# Printhead_board.net
KiCad netlist of a schematic drawn in EAGLE
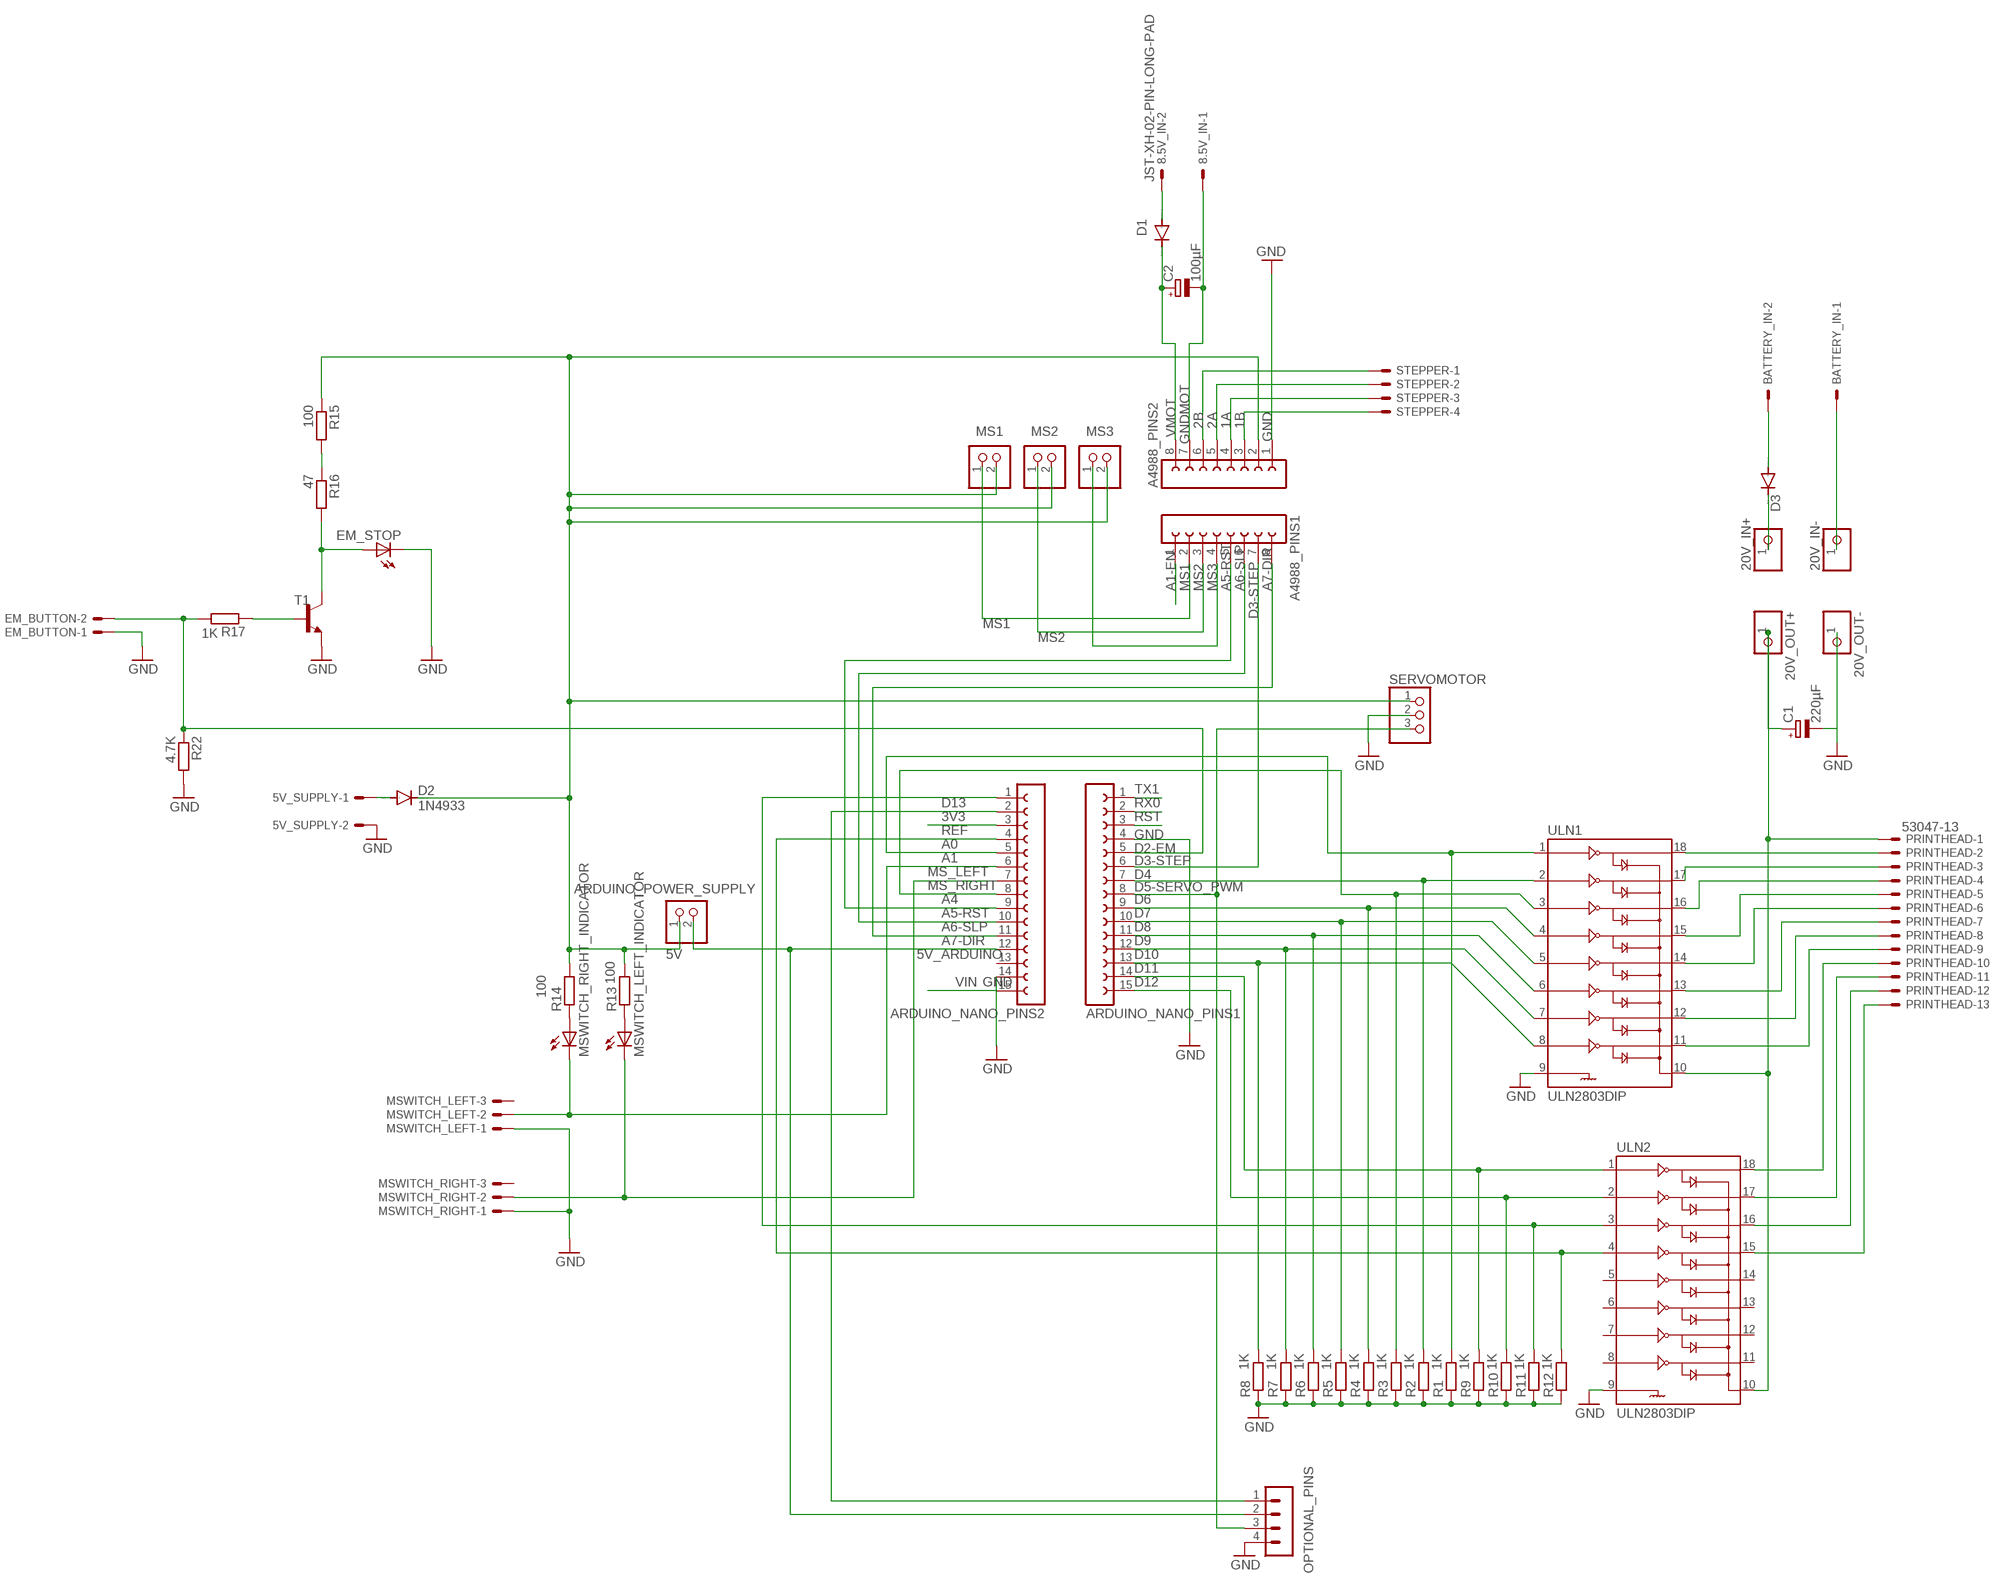
[diagram p0: schematic, sheet 1]

(export (version "E")
  (design (tool "Eeschema 10.0.6"))
  (components
    (comp (ref "5V_SUPPLY")
      (value "JST-XH-02-PIN-LONG-PAD")
      (footprint "eagle-import:JST-XH-02-PACKAGE-LONG-PAD")
      (libsource (lib "eagle-import") (part "JST-XH-02-PIN-LONG-PAD"))
    )
    (comp (ref "8.5V_IN")
      (value "JST-XH-02-PIN-LONG-PAD")
      (footprint "eagle-import:JST-XH-02-PACKAGE-LONG-PAD")
      (libsource (lib "eagle-import") (part "JST-XH-02-PIN-LONG-PAD"))
    )
    (comp (ref "20V_IN+")
      (value "PINHD-1X1")
      (footprint "eagle-import:1X01")
      (libsource (lib "eagle-import") (part "PINHD-1X1"))
    )
    (comp (ref "20V_IN-")
      (value "PINHD-1X1")
      (footprint "eagle-import:1X01")
      (libsource (lib "eagle-import") (part "PINHD-1X1"))
    )
    (comp (ref "20V_OUT+")
      (value "PINHD-1X1")
      (footprint "eagle-import:1X01")
      (libsource (lib "eagle-import") (part "PINHD-1X1"))
    )
    (comp (ref "20V_OUT-")
      (value "PINHD-1X1")
      (footprint "eagle-import:1X01")
      (libsource (lib "eagle-import") (part "PINHD-1X1"))
    )
    (comp (ref "A4988_PINS1")
      (value "FE08-1")
      (footprint "eagle-import:FE08")
      (libsource (lib "eagle-import") (part "FE08-1"))
    )
    (comp (ref "A4988_PINS2")
      (value "FE08-1")
      (footprint "eagle-import:FE08")
      (libsource (lib "eagle-import") (part "FE08-1"))
    )
    (comp (ref "ARDUINO_NANO_PINS1")
      (value "FE15-1")
      (footprint "eagle-import:FE15")
      (libsource (lib "eagle-import") (part "FE15-1"))
    )
    (comp (ref "ARDUINO_NANO_PINS2")
      (value "FE15-1")
      (footprint "eagle-import:FE15")
      (libsource (lib "eagle-import") (part "FE15-1"))
    )
    (comp (ref "ARDUINO_POWER_SUPPLY")
      (value "PINHD-1X2")
      (footprint "eagle-import:1X02")
      (libsource (lib "eagle-import") (part "PINHD-1X2"))
    )
    (comp (ref "BATTERY_IN")
      (value "JST-XH-02-PIN-ROUND-PAD")
      (footprint "eagle-import:JST-XH-02-PACKAGE-ROUND-PAD")
      (libsource (lib "eagle-import") (part "JST-XH-02-PIN-ROUND-PAD"))
    )
    (comp (ref "C1")
      (value "220µF")
      (footprint "eagle-import:E5-10,5")
      (libsource (lib "eagle-import") (part "CPOL-EUE5-10.5"))
    )
    (comp (ref "C2")
      (value "100µF")
      (footprint "eagle-import:SANYO-OSCON_E")
      (libsource (lib "eagle-import") (part "CPOL-EUSANYO_E"))
    )
    (comp (ref "D1")
      (value "DIODE-DO15-12")
      (footprint "eagle-import:DO15-12")
      (libsource (lib "eagle-import") (part "DIODE-DO15-12"))
    )
    (comp (ref "D2")
      (value "1N4933")
      (footprint "eagle-import:DO41-10")
      (libsource (lib "eagle-import") (part "1N4933"))
    )
    (comp (ref "D3")
      (value "DIODE-DO201-15")
      (footprint "eagle-import:DO201-15")
      (libsource (lib "eagle-import") (part "DIODE-DO201-15"))
    )
    (comp (ref "EM_BUTTON")
      (value "JST-XH-02-PIN-LONG-PAD")
      (footprint "eagle-import:JST-XH-02-PACKAGE-LONG-PAD")
      (libsource (lib "eagle-import") (part "JST-XH-02-PIN-LONG-PAD"))
    )
    (comp (ref "EM_STOP")
      (value "LED5MM")
      (footprint "eagle-import:LED5MM")
      (libsource (lib "eagle-import") (part "LED5MM"))
    )
    (comp (ref "MS1")
      (value "PINHD-1X2")
      (footprint "eagle-import:1X02")
      (libsource (lib "eagle-import") (part "PINHD-1X2"))
    )
    (comp (ref "MS2")
      (value "PINHD-1X2")
      (footprint "eagle-import:1X02")
      (libsource (lib "eagle-import") (part "PINHD-1X2"))
    )
    (comp (ref "MS3")
      (value "PINHD-1X2")
      (footprint "eagle-import:1X02")
      (libsource (lib "eagle-import") (part "PINHD-1X2"))
    )
    (comp (ref "MSWITCH_LEFT")
      (value "JST-XH-03-PIN-LONG-PAD")
      (footprint "eagle-import:JST-XH-03-PACKAGE-LONG-PAD")
      (libsource (lib "eagle-import") (part "JST-XH-03-PIN-LONG-PAD"))
    )
    (comp (ref "MSWITCH_LEFT_INDICATOR")
      (value "LED5MM")
      (footprint "eagle-import:LED5MM")
      (libsource (lib "eagle-import") (part "LED5MM"))
    )
    (comp (ref "MSWITCH_RIGHT")
      (value "JST-XH-03-PIN-LONG-PAD")
      (footprint "eagle-import:JST-XH-03-PACKAGE-LONG-PAD")
      (libsource (lib "eagle-import") (part "JST-XH-03-PIN-LONG-PAD"))
    )
    (comp (ref "MSWITCH_RIGHT_INDICATOR")
      (value "LED5MM")
      (footprint "eagle-import:LED5MM")
      (libsource (lib "eagle-import") (part "LED5MM"))
    )
    (comp (ref "OPTIONAL_PINS")
      (value "MA04-1")
      (footprint "eagle-import:MA04-1")
      (libsource (lib "eagle-import") (part "MA04-1"))
    )
    (comp (ref "PRINTHEAD")
      (value "53047-13")
      (footprint "eagle-import:53047-13")
      (fields (field (name "MF") "MOLEX") (field (name "MPN") "53047-1310-C"))
      (libsource (lib "eagle-import") (part "53?-13047"))
    )
    (comp (ref "R1")
      (value "1K")
      (footprint "eagle-import:0207_7")
      (libsource (lib "eagle-import") (part "R-EU_0207/7"))
    )
    (comp (ref "R2")
      (value "1K")
      (footprint "eagle-import:0207_7")
      (libsource (lib "eagle-import") (part "R-EU_0207/7"))
    )
    (comp (ref "R3")
      (value "1K")
      (footprint "eagle-import:0207_7")
      (libsource (lib "eagle-import") (part "R-EU_0207/7"))
    )
    (comp (ref "R4")
      (value "1K")
      (footprint "eagle-import:0207_7")
      (libsource (lib "eagle-import") (part "R-EU_0207/7"))
    )
    (comp (ref "R5")
      (value "1K")
      (footprint "eagle-import:0207_7")
      (libsource (lib "eagle-import") (part "R-EU_0207/7"))
    )
    (comp (ref "R6")
      (value "1K")
      (footprint "eagle-import:0207_7")
      (libsource (lib "eagle-import") (part "R-EU_0207/7"))
    )
    (comp (ref "R7")
      (value "1K")
      (footprint "eagle-import:0207_7")
      (libsource (lib "eagle-import") (part "R-EU_0207/7"))
    )
    (comp (ref "R8")
      (value "1K")
      (footprint "eagle-import:0207_7")
      (libsource (lib "eagle-import") (part "R-EU_0207/7"))
    )
    (comp (ref "R9")
      (value "1K")
      (footprint "eagle-import:0207_7")
      (libsource (lib "eagle-import") (part "R-EU_0207/7"))
    )
    (comp (ref "R10")
      (value "1K")
      (footprint "eagle-import:0207_7")
      (libsource (lib "eagle-import") (part "R-EU_0207/7"))
    )
    (comp (ref "R11")
      (value "1K")
      (footprint "eagle-import:0207_7")
      (libsource (lib "eagle-import") (part "R-EU_0207/7"))
    )
    (comp (ref "R12")
      (value "1K")
      (footprint "eagle-import:0207_7")
      (libsource (lib "eagle-import") (part "R-EU_0207/7"))
    )
    (comp (ref "R13")
      (value "100")
      (footprint "eagle-import:0207_7")
      (libsource (lib "eagle-import") (part "R-EU_0207/7"))
    )
    (comp (ref "R14")
      (value "100")
      (footprint "eagle-import:0207_7")
      (libsource (lib "eagle-import") (part "R-EU_0207/7"))
    )
    (comp (ref "R15")
      (value "100")
      (footprint "eagle-import:0207_7")
      (libsource (lib "eagle-import") (part "R-EU_0207/7"))
    )
    (comp (ref "R16")
      (value "47")
      (footprint "eagle-import:0207_7")
      (libsource (lib "eagle-import") (part "R-EU_0207/7"))
    )
    (comp (ref "R17")
      (value "1K")
      (footprint "eagle-import:0207_7")
      (libsource (lib "eagle-import") (part "R-EU_0207/7"))
    )
    (comp (ref "R22")
      (value "4.7K")
      (footprint "eagle-import:0207_7")
      (libsource (lib "eagle-import") (part "R-EU_0207/7"))
    )
    (comp (ref "SERVOMOTOR")
      (value "PINHD-1X3")
      (footprint "eagle-import:1X03")
      (libsource (lib "eagle-import") (part "PINHD-1X3"))
    )
    (comp (ref "STEPPER")
      (value "JST-XH-04-PIN-LONG-PAD")
      (footprint "eagle-import:JST-XH-04-PACKAGE-LONG-PAD")
      (libsource (lib "eagle-import") (part "JST-XH-04-PIN-LONG-PAD"))
    )
    (comp (ref "T1")
      (value "2N2222")
      (footprint "eagle-import:TO92-EBC-OVAL")
      (libsource (lib "eagle-import") (part "2N2222"))
    )
    (comp (ref "ULN1")
      (value "ULN2803DIP")
      (footprint "eagle-import:DIL18")
      (fields (field (name "MF") "STMicroelectronics") (field (name "MP") "ULN2803"))
      (libsource (lib "eagle-import") (part "ULN2803DIP"))
    )
    (comp (ref "ULN2")
      (value "ULN2803DIP")
      (footprint "eagle-import:DIL18")
      (fields (field (name "MF") "STMicroelectronics") (field (name "MP") "ULN2803"))
      (libsource (lib "eagle-import") (part "ULN2803DIP"))
    )
  )
  (nets
    (net (code "1") (name "/1A") (class "Default")
      (node (ref "A4988_PINS2") (pin "4") (pinfunction "4_4") (pintype "passive"))
      (node (ref "STEPPER") (pin "3") (pinfunction "S_3") (pintype "passive"))
    )
    (net (code "2") (name "/1B") (class "Default")
      (node (ref "A4988_PINS2") (pin "3") (pinfunction "3_3") (pintype "passive"))
      (node (ref "STEPPER") (pin "4") (pinfunction "S_4") (pintype "passive"))
    )
    (net (code "3") (name "/2A") (class "Default")
      (node (ref "A4988_PINS2") (pin "5") (pinfunction "5_5") (pintype "passive"))
      (node (ref "STEPPER") (pin "2") (pinfunction "S_2") (pintype "passive"))
    )
    (net (code "4") (name "/2B") (class "Default")
      (node (ref "A4988_PINS2") (pin "6") (pinfunction "6_6") (pintype "passive"))
      (node (ref "STEPPER") (pin "1") (pinfunction "S_1") (pintype "passive"))
    )
    (net (code "5") (name "/3V3") (class "Default")
      (node (ref "ARDUINO_NANO_PINS2") (pin "2") (pinfunction "2_2") (pintype "passive"))
      (node (ref "OPTIONAL_PINS") (pin "1") (pinfunction "1_1") (pintype "passive"))
    )
    (net (code "6") (name "/5V") (class "Default")
      (node (ref "A4988_PINS2") (pin "2") (pinfunction "2_2") (pintype "passive"))
      (node (ref "ARDUINO_POWER_SUPPLY") (pin "1") (pinfunction "1_1") (pintype "passive"))
      (node (ref "D2") (pin "C") (pinfunction "C_C") (pintype "passive"))
      (node (ref "MS1") (pin "2") (pinfunction "2_2") (pintype "passive"))
      (node (ref "MS2") (pin "2") (pinfunction "2_2") (pintype "passive"))
      (node (ref "MS3") (pin "2") (pinfunction "2_2") (pintype "passive"))
      (node (ref "R13") (pin "2") (pinfunction "2_2") (pintype "passive"))
      (node (ref "R14") (pin "2") (pinfunction "2_2") (pintype "passive"))
      (node (ref "R15") (pin "1") (pinfunction "1_1") (pintype "passive"))
      (node (ref "SERVOMOTOR") (pin "1") (pinfunction "1_1") (pintype "passive"))
    )
    (net (code "7") (name "/5V_ARDUINO") (class "Default")
      (node (ref "ARDUINO_NANO_PINS2") (pin "12") (pinfunction "12_12") (pintype "passive"))
      (node (ref "ARDUINO_POWER_SUPPLY") (pin "2") (pinfunction "2_2") (pintype "passive"))
      (node (ref "OPTIONAL_PINS") (pin "2") (pinfunction "2_2") (pintype "passive"))
    )
    (net (code "8") (name "/A0") (class "Default")
      (node (ref "ARDUINO_NANO_PINS2") (pin "4") (pinfunction "4_4") (pintype "passive"))
      (node (ref "R12") (pin "2") (pinfunction "2_2") (pintype "passive"))
      (node (ref "ULN2") (pin "4") (pinfunction "4_4") (pintype "bidirectional"))
    )
    (net (code "9") (name "/A1") (class "Default")
      (node (ref "ARDUINO_NANO_PINS2") (pin "5") (pinfunction "5_5") (pintype "passive"))
      (node (ref "R1") (pin "2") (pinfunction "2_2") (pintype "passive"))
      (node (ref "ULN1") (pin "1") (pinfunction "1_1") (pintype "bidirectional"))
    )
    (net (code "10") (name "/A1-EN") (class "Default")
      (node (ref "A4988_PINS1") (pin "1") (pinfunction "1_1") (pintype "passive"))
    )
    (net (code "11") (name "/A4") (class "Default")
      (node (ref "ARDUINO_NANO_PINS2") (pin "8") (pinfunction "8_8") (pintype "passive"))
      (node (ref "R3") (pin "2") (pinfunction "2_2") (pintype "passive"))
      (node (ref "ULN1") (pin "3") (pinfunction "3_3") (pintype "bidirectional"))
    )
    (net (code "12") (name "/A5-RST") (class "Default")
      (node (ref "A4988_PINS1") (pin "5") (pinfunction "5_5") (pintype "passive"))
      (node (ref "ARDUINO_NANO_PINS2") (pin "9") (pinfunction "9_9") (pintype "passive"))
    )
    (net (code "13") (name "/A6-SLP") (class "Default")
      (node (ref "A4988_PINS1") (pin "6") (pinfunction "6_6") (pintype "passive"))
      (node (ref "ARDUINO_NANO_PINS2") (pin "10") (pinfunction "10_10") (pintype "passive"))
    )
    (net (code "14") (name "/A7-DIR") (class "Default")
      (node (ref "A4988_PINS1") (pin "8") (pinfunction "8_8") (pintype "passive"))
      (node (ref "ARDUINO_NANO_PINS2") (pin "11") (pinfunction "11_11") (pintype "passive"))
    )
    (net (code "15") (name "/D2-EM") (class "Default")
      (node (ref "ARDUINO_NANO_PINS1") (pin "5") (pinfunction "5_5") (pintype "passive"))
      (node (ref "EM_BUTTON") (pin "2") (pinfunction "S_2") (pintype "passive"))
      (node (ref "R17") (pin "2") (pinfunction "2_2") (pintype "passive"))
      (node (ref "R22") (pin "1") (pinfunction "1_1") (pintype "passive"))
    )
    (net (code "16") (name "/D3-STEP") (class "Default")
      (node (ref "A4988_PINS1") (pin "7") (pinfunction "7_7") (pintype "passive"))
      (node (ref "ARDUINO_NANO_PINS1") (pin "6") (pinfunction "6_6") (pintype "passive"))
    )
    (net (code "17") (name "/D4") (class "Default")
      (node (ref "ARDUINO_NANO_PINS1") (pin "7") (pinfunction "7_7") (pintype "passive"))
      (node (ref "R2") (pin "2") (pinfunction "2_2") (pintype "passive"))
      (node (ref "ULN1") (pin "2") (pinfunction "2_2") (pintype "bidirectional"))
    )
    (net (code "18") (name "/D5-SERVO_PWM") (class "Default")
      (node (ref "ARDUINO_NANO_PINS1") (pin "8") (pinfunction "8_8") (pintype "passive"))
      (node (ref "OPTIONAL_PINS") (pin "3") (pinfunction "3_3") (pintype "passive"))
      (node (ref "SERVOMOTOR") (pin "3") (pinfunction "3_3") (pintype "passive"))
    )
    (net (code "19") (name "/D6") (class "Default")
      (node (ref "ARDUINO_NANO_PINS1") (pin "9") (pinfunction "9_9") (pintype "passive"))
      (node (ref "R4") (pin "2") (pinfunction "2_2") (pintype "passive"))
      (node (ref "ULN1") (pin "4") (pinfunction "4_4") (pintype "bidirectional"))
    )
    (net (code "20") (name "/D7") (class "Default")
      (node (ref "ARDUINO_NANO_PINS1") (pin "10") (pinfunction "10_10") (pintype "passive"))
      (node (ref "R5") (pin "2") (pinfunction "2_2") (pintype "passive"))
      (node (ref "ULN1") (pin "5") (pinfunction "5_5") (pintype "bidirectional"))
    )
    (net (code "21") (name "/D8") (class "Default")
      (node (ref "ARDUINO_NANO_PINS1") (pin "11") (pinfunction "11_11") (pintype "passive"))
      (node (ref "R6") (pin "2") (pinfunction "2_2") (pintype "passive"))
      (node (ref "ULN1") (pin "6") (pinfunction "6_6") (pintype "bidirectional"))
    )
    (net (code "22") (name "/D9") (class "Default")
      (node (ref "ARDUINO_NANO_PINS1") (pin "12") (pinfunction "12_12") (pintype "passive"))
      (node (ref "R7") (pin "2") (pinfunction "2_2") (pintype "passive"))
      (node (ref "ULN1") (pin "7") (pinfunction "7_7") (pintype "bidirectional"))
    )
    (net (code "23") (name "/D10") (class "Default")
      (node (ref "ARDUINO_NANO_PINS1") (pin "13") (pinfunction "13_13") (pintype "passive"))
      (node (ref "R8") (pin "2") (pinfunction "2_2") (pintype "passive"))
      (node (ref "ULN1") (pin "8") (pinfunction "8_8") (pintype "bidirectional"))
    )
    (net (code "24") (name "/D11") (class "Default")
      (node (ref "ARDUINO_NANO_PINS1") (pin "14") (pinfunction "14_14") (pintype "passive"))
      (node (ref "R9") (pin "2") (pinfunction "2_2") (pintype "passive"))
      (node (ref "ULN2") (pin "1") (pinfunction "1_1") (pintype "bidirectional"))
    )
    (net (code "25") (name "/D12") (class "Default")
      (node (ref "ARDUINO_NANO_PINS1") (pin "15") (pinfunction "15_15") (pintype "passive"))
      (node (ref "R10") (pin "2") (pinfunction "2_2") (pintype "passive"))
      (node (ref "ULN2") (pin "2") (pinfunction "2_2") (pintype "bidirectional"))
    )
    (net (code "26") (name "/D13") (class "Default")
      (node (ref "ARDUINO_NANO_PINS2") (pin "1") (pinfunction "1_1") (pintype "passive"))
      (node (ref "R11") (pin "2") (pinfunction "2_2") (pintype "passive"))
      (node (ref "ULN2") (pin "3") (pinfunction "3_3") (pintype "bidirectional"))
    )
    (net (code "27") (name "/GNDMOT") (class "Default")
      (node (ref "8.5V_IN") (pin "1") (pinfunction "S_1") (pintype "passive"))
      (node (ref "A4988_PINS2") (pin "7") (pinfunction "7_7") (pintype "passive"))
      (node (ref "C2") (pin "-") (pinfunction "-_-") (pintype "passive"))
    )
    (net (code "28") (name "/MS1") (class "Default")
      (node (ref "A4988_PINS1") (pin "2") (pinfunction "2_2") (pintype "passive"))
      (node (ref "MS1") (pin "1") (pinfunction "1_1") (pintype "passive"))
    )
    (net (code "29") (name "/MS2") (class "Default")
      (node (ref "A4988_PINS1") (pin "3") (pinfunction "3_3") (pintype "passive"))
      (node (ref "MS2") (pin "1") (pinfunction "1_1") (pintype "passive"))
    )
    (net (code "30") (name "/MS3") (class "Default")
      (node (ref "A4988_PINS1") (pin "4") (pinfunction "4_4") (pintype "passive"))
      (node (ref "MS3") (pin "1") (pinfunction "1_1") (pintype "passive"))
    )
    (net (code "31") (name "/MS_LEFT") (class "Default")
      (node (ref "ARDUINO_NANO_PINS2") (pin "6") (pinfunction "6_6") (pintype "passive"))
      (node (ref "MSWITCH_LEFT") (pin "2") (pinfunction "S_2") (pintype "passive"))
      (node (ref "MSWITCH_RIGHT_INDICATOR") (pin "K") (pinfunction "C_K") (pintype "passive"))
    )
    (net (code "32") (name "/MS_RIGHT") (class "Default")
      (node (ref "ARDUINO_NANO_PINS2") (pin "7") (pinfunction "7_7") (pintype "passive"))
      (node (ref "MSWITCH_LEFT_INDICATOR") (pin "K") (pinfunction "C_K") (pintype "passive"))
      (node (ref "MSWITCH_RIGHT") (pin "2") (pinfunction "S_2") (pintype "passive"))
    )
    (net (code "33") (name "/REF") (class "Default")
      (node (ref "ARDUINO_NANO_PINS2") (pin "3") (pinfunction "3_3") (pintype "passive"))
    )
    (net (code "34") (name "/RST") (class "Default")
      (node (ref "ARDUINO_NANO_PINS1") (pin "3") (pinfunction "3_3") (pintype "passive"))
    )
    (net (code "35") (name "/RX0") (class "Default")
      (node (ref "ARDUINO_NANO_PINS1") (pin "2") (pinfunction "2_2") (pintype "passive"))
    )
    (net (code "36") (name "/TX1") (class "Default")
      (node (ref "ARDUINO_NANO_PINS1") (pin "1") (pinfunction "1_1") (pintype "passive"))
    )
    (net (code "37") (name "/VIN") (class "Default")
      (node (ref "ARDUINO_NANO_PINS2") (pin "15") (pinfunction "15_15") (pintype "passive"))
    )
    (net (code "38") (name "/VMOT") (class "Default")
      (node (ref "A4988_PINS2") (pin "8") (pinfunction "8_8") (pintype "passive"))
      (node (ref "C2") (pin "+") (pinfunction "+_+") (pintype "passive"))
      (node (ref "D1") (pin "C") (pinfunction "C_C") (pintype "passive"))
    )
    (net (code "39") (name "GND") (class "Default")
      (node (ref "20V_OUT-") (pin "1") (pinfunction "1_1") (pintype "passive"))
      (node (ref "5V_SUPPLY") (pin "2") (pinfunction "S_2") (pintype "passive"))
      (node (ref "A4988_PINS2") (pin "1") (pinfunction "1_1") (pintype "passive"))
      (node (ref "ARDUINO_NANO_PINS1") (pin "4") (pinfunction "4_4") (pintype "passive"))
      (node (ref "ARDUINO_NANO_PINS2") (pin "14") (pinfunction "14_14") (pintype "passive"))
      (node (ref "C1") (pin "-") (pinfunction "-_-") (pintype "passive"))
      (node (ref "EM_BUTTON") (pin "1") (pinfunction "S_1") (pintype "passive"))
      (node (ref "EM_STOP") (pin "K") (pinfunction "C_K") (pintype "passive"))
      (node (ref "MSWITCH_LEFT") (pin "1") (pinfunction "S_1") (pintype "passive"))
      (node (ref "MSWITCH_RIGHT") (pin "1") (pinfunction "S_1") (pintype "passive"))
      (node (ref "OPTIONAL_PINS") (pin "4") (pinfunction "4_4") (pintype "passive"))
      (node (ref "R1") (pin "1") (pinfunction "1_1") (pintype "passive"))
      (node (ref "R10") (pin "1") (pinfunction "1_1") (pintype "passive"))
      (node (ref "R11") (pin "1") (pinfunction "1_1") (pintype "passive"))
      (node (ref "R12") (pin "1") (pinfunction "1_1") (pintype "passive"))
      (node (ref "R2") (pin "1") (pinfunction "1_1") (pintype "passive"))
      (node (ref "R22") (pin "2") (pinfunction "2_2") (pintype "passive"))
      (node (ref "R3") (pin "1") (pinfunction "1_1") (pintype "passive"))
      (node (ref "R4") (pin "1") (pinfunction "1_1") (pintype "passive"))
      (node (ref "R5") (pin "1") (pinfunction "1_1") (pintype "passive"))
      (node (ref "R6") (pin "1") (pinfunction "1_1") (pintype "passive"))
      (node (ref "R7") (pin "1") (pinfunction "1_1") (pintype "passive"))
      (node (ref "R8") (pin "1") (pinfunction "1_1") (pintype "passive"))
      (node (ref "R9") (pin "1") (pinfunction "1_1") (pintype "passive"))
      (node (ref "SERVOMOTOR") (pin "2") (pinfunction "2_2") (pintype "passive"))
      (node (ref "T1") (pin "E") (pinfunction "E_E") (pintype "passive"))
      (node (ref "ULN1") (pin "9") (pinfunction "9_9") (pintype "bidirectional"))
      (node (ref "ULN2") (pin "9") (pinfunction "9_9") (pintype "bidirectional"))
    )
    (net (code "40") (name "Net-(5V_SUPPLYA-S)") (class "Default")
      (node (ref "5V_SUPPLY") (pin "1") (pinfunction "S_1") (pintype "passive"))
      (node (ref "D2") (pin "A") (pinfunction "A_A") (pintype "passive"))
    )
    (net (code "41") (name "Net-(8.5V_INB-S)") (class "Default")
      (node (ref "8.5V_IN") (pin "2") (pinfunction "S_2") (pintype "passive"))
      (node (ref "D1") (pin "A") (pinfunction "A_A") (pintype "passive"))
    )
    (net (code "42") (name "Net-(20V_IN+-Pad1)") (class "Default")
      (node (ref "20V_IN+") (pin "1") (pinfunction "1_1") (pintype "passive"))
      (node (ref "D3") (pin "C") (pinfunction "C_C") (pintype "passive"))
    )
    (net (code "43") (name "Net-(BATTERY_INA-S)") (class "Default")
      (node (ref "20V_IN-") (pin "1") (pinfunction "1_1") (pintype "passive"))
      (node (ref "BATTERY_IN") (pin "1") (pinfunction "S_1") (pintype "passive"))
    )
    (net (code "44") (name "Net-(BATTERY_INB-S)") (class "Default")
      (node (ref "BATTERY_IN") (pin "2") (pinfunction "S_2") (pintype "passive"))
      (node (ref "D3") (pin "A") (pinfunction "A_A") (pintype "passive"))
    )
    (net (code "45") (name "Net-(EM_STOP-PadA)") (class "Default")
      (node (ref "EM_STOP") (pin "A") (pinfunction "A_A") (pintype "passive"))
      (node (ref "R16") (pin "2") (pinfunction "2_2") (pintype "passive"))
      (node (ref "T1") (pin "C") (pinfunction "C_C") (pintype "passive"))
    )
    (net (code "46") (name "Net-(MSWITCH_LEFT_INDICATOR-PadA)") (class "Default")
      (node (ref "MSWITCH_LEFT_INDICATOR") (pin "A") (pinfunction "A_A") (pintype "passive"))
      (node (ref "R13") (pin "1") (pinfunction "1_1") (pintype "passive"))
    )
    (net (code "47") (name "Net-(MSWITCH_RIGHT_INDICATOR-PadA)") (class "Default")
      (node (ref "MSWITCH_RIGHT_INDICATOR") (pin "A") (pinfunction "A_A") (pintype "passive"))
      (node (ref "R14") (pin "1") (pinfunction "1_1") (pintype "passive"))
    )
    (net (code "48") (name "Net-(PRINTHEADA-S)") (class "Default")
      (node (ref "20V_OUT+") (pin "1") (pinfunction "1_1") (pintype "passive"))
      (node (ref "C1") (pin "+") (pinfunction "+_+") (pintype "passive"))
      (node (ref "PRINTHEAD") (pin "1") (pinfunction "S_1") (pintype "passive"))
      (node (ref "ULN1") (pin "10") (pinfunction "10_10") (pintype "bidirectional"))
      (node (ref "ULN2") (pin "10") (pinfunction "10_10") (pintype "bidirectional"))
    )
    (net (code "49") (name "Net-(PRINTHEADB-S)") (class "Default")
      (node (ref "PRINTHEAD") (pin "10") (pinfunction "S_10") (pintype "passive"))
      (node (ref "ULN2") (pin "18") (pinfunction "18_18") (pintype "bidirectional"))
    )
    (net (code "50") (name "Net-(PRINTHEADC-S)") (class "Default")
      (node (ref "PRINTHEAD") (pin "11") (pinfunction "S_11") (pintype "passive"))
      (node (ref "ULN2") (pin "17") (pinfunction "17_17") (pintype "bidirectional"))
    )
    (net (code "51") (name "Net-(PRINTHEADD-S)") (class "Default")
      (node (ref "PRINTHEAD") (pin "12") (pinfunction "S_12") (pintype "passive"))
      (node (ref "ULN2") (pin "16") (pinfunction "16_16") (pintype "bidirectional"))
    )
    (net (code "52") (name "Net-(PRINTHEADE-S)") (class "Default")
      (node (ref "PRINTHEAD") (pin "13") (pinfunction "S_13") (pintype "passive"))
      (node (ref "ULN2") (pin "15") (pinfunction "15_15") (pintype "bidirectional"))
    )
    (net (code "53") (name "Net-(PRINTHEADF-S)") (class "Default")
      (node (ref "PRINTHEAD") (pin "2") (pinfunction "S_2") (pintype "passive"))
      (node (ref "ULN1") (pin "18") (pinfunction "18_18") (pintype "bidirectional"))
    )
    (net (code "54") (name "Net-(PRINTHEADG-S)") (class "Default")
      (node (ref "PRINTHEAD") (pin "3") (pinfunction "S_3") (pintype "passive"))
      (node (ref "ULN1") (pin "17") (pinfunction "17_17") (pintype "bidirectional"))
    )
    (net (code "55") (name "Net-(PRINTHEADH-S)") (class "Default")
      (node (ref "PRINTHEAD") (pin "4") (pinfunction "S_4") (pintype "passive"))
      (node (ref "ULN1") (pin "16") (pinfunction "16_16") (pintype "bidirectional"))
    )
    (net (code "56") (name "Net-(PRINTHEADI-S)") (class "Default")
      (node (ref "PRINTHEAD") (pin "5") (pinfunction "S_5") (pintype "passive"))
      (node (ref "ULN1") (pin "15") (pinfunction "15_15") (pintype "bidirectional"))
    )
    (net (code "57") (name "Net-(PRINTHEADJ-S)") (class "Default")
      (node (ref "PRINTHEAD") (pin "6") (pinfunction "S_6") (pintype "passive"))
      (node (ref "ULN1") (pin "14") (pinfunction "14_14") (pintype "bidirectional"))
    )
    (net (code "58") (name "Net-(PRINTHEADK-S)") (class "Default")
      (node (ref "PRINTHEAD") (pin "7") (pinfunction "S_7") (pintype "passive"))
      (node (ref "ULN1") (pin "13") (pinfunction "13_13") (pintype "bidirectional"))
    )
    (net (code "59") (name "Net-(PRINTHEADL-S)") (class "Default")
      (node (ref "PRINTHEAD") (pin "8") (pinfunction "S_8") (pintype "passive"))
      (node (ref "ULN1") (pin "12") (pinfunction "12_12") (pintype "bidirectional"))
    )
    (net (code "60") (name "Net-(PRINTHEADM-S)") (class "Default")
      (node (ref "PRINTHEAD") (pin "9") (pinfunction "S_9") (pintype "passive"))
      (node (ref "ULN1") (pin "11") (pinfunction "11_11") (pintype "bidirectional"))
    )
    (net (code "61") (name "Net-(R15-Pad2)") (class "Default")
      (node (ref "R15") (pin "2") (pinfunction "2_2") (pintype "passive"))
      (node (ref "R16") (pin "1") (pinfunction "1_1") (pintype "passive"))
    )
    (net (code "62") (name "Net-(R17-Pad1)") (class "Default")
      (node (ref "R17") (pin "1") (pinfunction "1_1") (pintype "passive"))
      (node (ref "T1") (pin "B") (pinfunction "B_B") (pintype "passive"))
    )
    (net (code "63") (name "unconnected-(ARDUINO_NANO_PINS2-Pad13)") (class "Default")
      (node (ref "ARDUINO_NANO_PINS2") (pin "13") (pinfunction "13_13") (pintype "passive"))
    )
    (net (code "64") (name "unconnected-(MSWITCH_LEFTC-S-Pad3)") (class "Default")
      (node (ref "MSWITCH_LEFT") (pin "3") (pinfunction "S_3") (pintype "passive"))
    )
    (net (code "65") (name "unconnected-(MSWITCH_RIGHTC-S-Pad3)") (class "Default")
      (node (ref "MSWITCH_RIGHT") (pin "3") (pinfunction "S_3") (pintype "passive"))
    )
    (net (code "66") (name "unconnected-(ULN2-Pad5)") (class "Default")
      (node (ref "ULN2") (pin "5") (pinfunction "5_5") (pintype "bidirectional"))
    )
    (net (code "67") (name "unconnected-(ULN2-Pad6)") (class "Default")
      (node (ref "ULN2") (pin "6") (pinfunction "6_6") (pintype "bidirectional"))
    )
    (net (code "68") (name "unconnected-(ULN2-Pad7)") (class "Default")
      (node (ref "ULN2") (pin "7") (pinfunction "7_7") (pintype "bidirectional"))
    )
    (net (code "69") (name "unconnected-(ULN2-Pad8)") (class "Default")
      (node (ref "ULN2") (pin "8") (pinfunction "8_8") (pintype "bidirectional"))
    )
    (net (code "70") (name "unconnected-(ULN2-Pad11)") (class "Default")
      (node (ref "ULN2") (pin "11") (pinfunction "11_11") (pintype "bidirectional"))
    )
    (net (code "71") (name "unconnected-(ULN2-Pad12)") (class "Default")
      (node (ref "ULN2") (pin "12") (pinfunction "12_12") (pintype "bidirectional"))
    )
    (net (code "72") (name "unconnected-(ULN2-Pad13)") (class "Default")
      (node (ref "ULN2") (pin "13") (pinfunction "13_13") (pintype "bidirectional"))
    )
    (net (code "73") (name "unconnected-(ULN2-Pad14)") (class "Default")
      (node (ref "ULN2") (pin "14") (pinfunction "14_14") (pintype "bidirectional"))
    )
  )
)
